# LED.net
KiCad netlist of a schematic drawn in Altium Designer
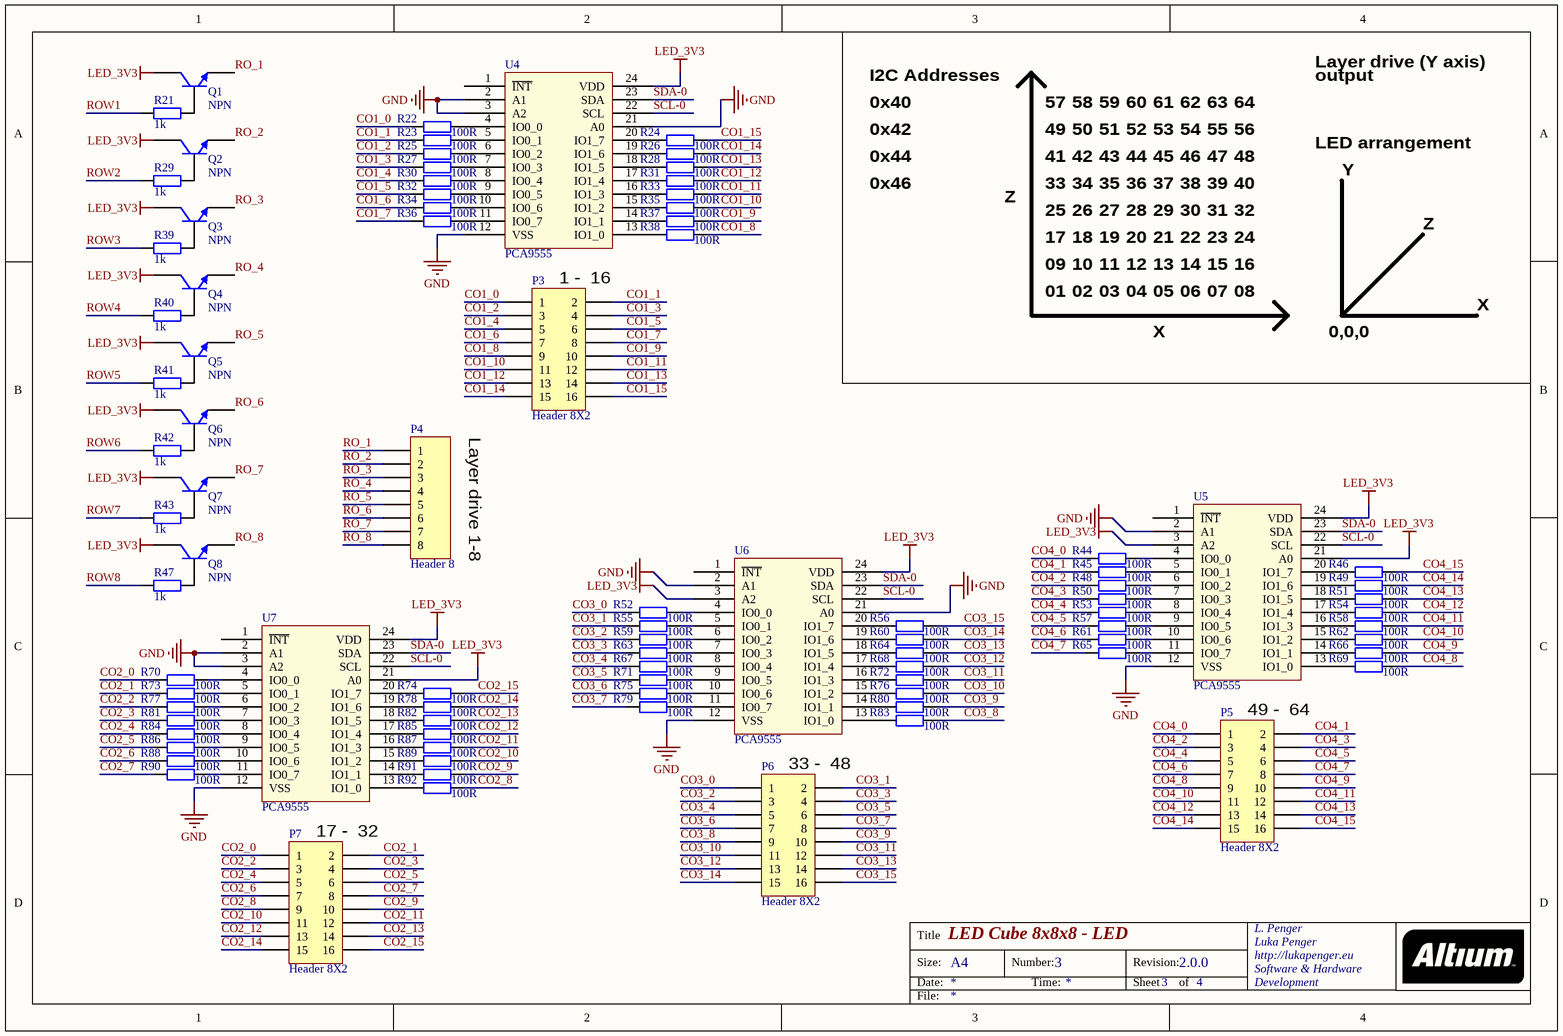
[diagram p0: LED.SchDoc]

(export (version "E")
  (design (tool "Eeschema 10.0.6"))
  (components
    (comp (ref "P3")
      (value "Header 8X2")
      (footprint "IDC-2x8")
      (description "Header, 8-Pin, Dual row")
      (fields (field (name "PUBLISHER") "Altium Limited"))
      (libsource (lib "Miscellaneous Connectors") (part "Header 8X2"))
    )
    (comp (ref "P4")
      (value "Header 8")
      (footprint "IDC-2x4")
      (description "Header, 8-Pin")
      (fields (field (name "PUBLISHER") "Altium Limited"))
      (libsource (lib "Miscellaneous Connectors") (part "Header 8"))
    )
    (comp (ref "P5")
      (value "Header 8X2")
      (footprint "IDC-2x8")
      (description "Header, 8-Pin, Dual row")
      (fields (field (name "PUBLISHER") "Altium Limited"))
      (libsource (lib "Miscellaneous Connectors") (part "Header 8X2"))
    )
    (comp (ref "P6")
      (value "Header 8X2")
      (footprint "IDC-2x8")
      (description "Header, 8-Pin, Dual row")
      (fields (field (name "PUBLISHER") "Altium Limited"))
      (libsource (lib "Miscellaneous Connectors") (part "Header 8X2"))
    )
    (comp (ref "P7")
      (value "Header 8X2")
      (footprint "IDC-2x8")
      (description "Header, 8-Pin, Dual row")
      (fields (field (name "PUBLISHER") "Altium Limited"))
      (libsource (lib "Miscellaneous Connectors") (part "Header 8X2"))
    )
    (comp (ref "Q1")
      (value "NPN")
      (footprint "SOT89N")
      (description "NPN Bipolar Transistor")
      (fields (field (name "PUBLISHER") "Altium Limited"))
      (libsource (lib "Miscellaneous Devices") (part "NPN"))
    )
    (comp (ref "Q2")
      (value "NPN")
      (footprint "SOT89N")
      (description "NPN Bipolar Transistor")
      (fields (field (name "PUBLISHER") "Altium Limited"))
      (libsource (lib "Miscellaneous Devices") (part "NPN"))
    )
    (comp (ref "Q3")
      (value "NPN")
      (footprint "SOT89N")
      (description "NPN Bipolar Transistor")
      (fields (field (name "PUBLISHER") "Altium Limited"))
      (libsource (lib "Miscellaneous Devices") (part "NPN"))
    )
    (comp (ref "Q4")
      (value "NPN")
      (footprint "SOT89N")
      (description "NPN Bipolar Transistor")
      (fields (field (name "PUBLISHER") "Altium Limited"))
      (libsource (lib "Miscellaneous Devices") (part "NPN"))
    )
    (comp (ref "Q5")
      (value "NPN")
      (footprint "SOT89N")
      (description "NPN Bipolar Transistor")
      (fields (field (name "PUBLISHER") "Altium Limited"))
      (libsource (lib "Miscellaneous Devices") (part "NPN"))
    )
    (comp (ref "Q6")
      (value "NPN")
      (footprint "SOT89N")
      (description "NPN Bipolar Transistor")
      (fields (field (name "PUBLISHER") "Altium Limited"))
      (libsource (lib "Miscellaneous Devices") (part "NPN"))
    )
    (comp (ref "Q7")
      (value "NPN")
      (footprint "SOT89N")
      (description "NPN Bipolar Transistor")
      (fields (field (name "PUBLISHER") "Altium Limited"))
      (libsource (lib "Miscellaneous Devices") (part "NPN"))
    )
    (comp (ref "Q8")
      (value "NPN")
      (footprint "SOT89N")
      (description "NPN Bipolar Transistor")
      (fields (field (name "PUBLISHER") "Altium Limited"))
      (libsource (lib "Miscellaneous Devices") (part "NPN"))
    )
    (comp (ref "R21")
      (value "1k")
      (footprint "6-0805_N")
      (description "Resistor")
      (fields (field (name "PUBLISHER") "Altium Limited"))
      (libsource (lib "") (part "Res2_1"))
    )
    (comp (ref "R22")
      (value "100R")
      (footprint "6-0805_N")
      (description "Resistor")
      (fields (field (name "PUBLISHER") "Altium Limited"))
      (libsource (lib "Miscellaneous Devices") (part "Res2"))
    )
    (comp (ref "R23")
      (value "100R")
      (footprint "6-0805_N")
      (description "Resistor")
      (fields (field (name "PUBLISHER") "Altium Limited"))
      (libsource (lib "Miscellaneous Devices") (part "Res2"))
    )
    (comp (ref "R24")
      (value "100R")
      (footprint "6-0805_N")
      (description "Resistor")
      (fields (field (name "PUBLISHER") "Altium Limited"))
      (libsource (lib "Miscellaneous Devices") (part "Res2"))
    )
    (comp (ref "R25")
      (value "100R")
      (footprint "6-0805_N")
      (description "Resistor")
      (fields (field (name "PUBLISHER") "Altium Limited"))
      (libsource (lib "Miscellaneous Devices") (part "Res2"))
    )
    (comp (ref "R26")
      (value "100R")
      (footprint "6-0805_N")
      (description "Resistor")
      (fields (field (name "PUBLISHER") "Altium Limited"))
      (libsource (lib "Miscellaneous Devices") (part "Res2"))
    )
    (comp (ref "R27")
      (value "100R")
      (footprint "6-0805_N")
      (description "Resistor")
      (fields (field (name "PUBLISHER") "Altium Limited"))
      (libsource (lib "Miscellaneous Devices") (part "Res2"))
    )
    (comp (ref "R28")
      (value "100R")
      (footprint "6-0805_N")
      (description "Resistor")
      (fields (field (name "PUBLISHER") "Altium Limited"))
      (libsource (lib "Miscellaneous Devices") (part "Res2"))
    )
    (comp (ref "R29")
      (value "1k")
      (footprint "6-0805_N")
      (description "Resistor")
      (fields (field (name "PUBLISHER") "Altium Limited"))
      (libsource (lib "") (part "Res2_1"))
    )
    (comp (ref "R30")
      (value "100R")
      (footprint "6-0805_N")
      (description "Resistor")
      (fields (field (name "PUBLISHER") "Altium Limited"))
      (libsource (lib "Miscellaneous Devices") (part "Res2"))
    )
    (comp (ref "R31")
      (value "100R")
      (footprint "6-0805_N")
      (description "Resistor")
      (fields (field (name "PUBLISHER") "Altium Limited"))
      (libsource (lib "Miscellaneous Devices") (part "Res2"))
    )
    (comp (ref "R32")
      (value "100R")
      (footprint "6-0805_N")
      (description "Resistor")
      (fields (field (name "PUBLISHER") "Altium Limited"))
      (libsource (lib "Miscellaneous Devices") (part "Res2"))
    )
    (comp (ref "R33")
      (value "100R")
      (footprint "6-0805_N")
      (description "Resistor")
      (fields (field (name "PUBLISHER") "Altium Limited"))
      (libsource (lib "Miscellaneous Devices") (part "Res2"))
    )
    (comp (ref "R34")
      (value "100R")
      (footprint "6-0805_N")
      (description "Resistor")
      (fields (field (name "PUBLISHER") "Altium Limited"))
      (libsource (lib "Miscellaneous Devices") (part "Res2"))
    )
    (comp (ref "R35")
      (value "100R")
      (footprint "6-0805_N")
      (description "Resistor")
      (fields (field (name "PUBLISHER") "Altium Limited"))
      (libsource (lib "Miscellaneous Devices") (part "Res2"))
    )
    (comp (ref "R36")
      (value "100R")
      (footprint "6-0805_N")
      (description "Resistor")
      (fields (field (name "PUBLISHER") "Altium Limited"))
      (libsource (lib "Miscellaneous Devices") (part "Res2"))
    )
    (comp (ref "R37")
      (value "100R")
      (footprint "6-0805_N")
      (description "Resistor")
      (fields (field (name "PUBLISHER") "Altium Limited"))
      (libsource (lib "Miscellaneous Devices") (part "Res2"))
    )
    (comp (ref "R38")
      (value "100R")
      (footprint "6-0805_N")
      (description "Resistor")
      (fields (field (name "PUBLISHER") "Altium Limited"))
      (libsource (lib "Miscellaneous Devices") (part "Res2"))
    )
    (comp (ref "R39")
      (value "1k")
      (footprint "6-0805_N")
      (description "Resistor")
      (fields (field (name "PUBLISHER") "Altium Limited"))
      (libsource (lib "") (part "Res2_1"))
    )
    (comp (ref "R40")
      (value "1k")
      (footprint "6-0805_N")
      (description "Resistor")
      (fields (field (name "PUBLISHER") "Altium Limited"))
      (libsource (lib "") (part "Res2_1"))
    )
    (comp (ref "R41")
      (value "1k")
      (footprint "6-0805_N")
      (description "Resistor")
      (fields (field (name "PUBLISHER") "Altium Limited"))
      (libsource (lib "") (part "Res2_1"))
    )
    (comp (ref "R42")
      (value "1k")
      (footprint "6-0805_N")
      (description "Resistor")
      (fields (field (name "PUBLISHER") "Altium Limited"))
      (libsource (lib "") (part "Res2_1"))
    )
    (comp (ref "R43")
      (value "1k")
      (footprint "6-0805_N")
      (description "Resistor")
      (fields (field (name "PUBLISHER") "Altium Limited"))
      (libsource (lib "") (part "Res2_1"))
    )
    (comp (ref "R44")
      (value "100R")
      (footprint "6-0805_N")
      (description "Resistor")
      (fields (field (name "PUBLISHER") "Altium Limited"))
      (libsource (lib "Miscellaneous Devices") (part "Res2"))
    )
    (comp (ref "R45")
      (value "100R")
      (footprint "6-0805_N")
      (description "Resistor")
      (fields (field (name "PUBLISHER") "Altium Limited"))
      (libsource (lib "Miscellaneous Devices") (part "Res2"))
    )
    (comp (ref "R46")
      (value "100R")
      (footprint "6-0805_N")
      (description "Resistor")
      (fields (field (name "PUBLISHER") "Altium Limited"))
      (libsource (lib "Miscellaneous Devices") (part "Res2"))
    )
    (comp (ref "R47")
      (value "1k")
      (footprint "6-0805_N")
      (description "Resistor")
      (fields (field (name "PUBLISHER") "Altium Limited"))
      (libsource (lib "") (part "Res2_1"))
    )
    (comp (ref "R48")
      (value "100R")
      (footprint "6-0805_N")
      (description "Resistor")
      (fields (field (name "PUBLISHER") "Altium Limited"))
      (libsource (lib "Miscellaneous Devices") (part "Res2"))
    )
    (comp (ref "R49")
      (value "100R")
      (footprint "6-0805_N")
      (description "Resistor")
      (fields (field (name "PUBLISHER") "Altium Limited"))
      (libsource (lib "Miscellaneous Devices") (part "Res2"))
    )
    (comp (ref "R50")
      (value "100R")
      (footprint "6-0805_N")
      (description "Resistor")
      (fields (field (name "PUBLISHER") "Altium Limited"))
      (libsource (lib "Miscellaneous Devices") (part "Res2"))
    )
    (comp (ref "R51")
      (value "100R")
      (footprint "6-0805_N")
      (description "Resistor")
      (fields (field (name "PUBLISHER") "Altium Limited"))
      (libsource (lib "Miscellaneous Devices") (part "Res2"))
    )
    (comp (ref "R52")
      (value "100R")
      (footprint "6-0805_N")
      (description "Resistor")
      (fields (field (name "PUBLISHER") "Altium Limited"))
      (libsource (lib "Miscellaneous Devices") (part "Res2"))
    )
    (comp (ref "R53")
      (value "100R")
      (footprint "6-0805_N")
      (description "Resistor")
      (fields (field (name "PUBLISHER") "Altium Limited"))
      (libsource (lib "Miscellaneous Devices") (part "Res2"))
    )
    (comp (ref "R54")
      (value "100R")
      (footprint "6-0805_N")
      (description "Resistor")
      (fields (field (name "PUBLISHER") "Altium Limited"))
      (libsource (lib "Miscellaneous Devices") (part "Res2"))
    )
    (comp (ref "R55")
      (value "100R")
      (footprint "6-0805_N")
      (description "Resistor")
      (fields (field (name "PUBLISHER") "Altium Limited"))
      (libsource (lib "Miscellaneous Devices") (part "Res2"))
    )
    (comp (ref "R56")
      (value "100R")
      (footprint "6-0805_N")
      (description "Resistor")
      (fields (field (name "PUBLISHER") "Altium Limited"))
      (libsource (lib "Miscellaneous Devices") (part "Res2"))
    )
    (comp (ref "R57")
      (value "100R")
      (footprint "6-0805_N")
      (description "Resistor")
      (fields (field (name "PUBLISHER") "Altium Limited"))
      (libsource (lib "Miscellaneous Devices") (part "Res2"))
    )
    (comp (ref "R58")
      (value "100R")
      (footprint "6-0805_N")
      (description "Resistor")
      (fields (field (name "PUBLISHER") "Altium Limited"))
      (libsource (lib "Miscellaneous Devices") (part "Res2"))
    )
    (comp (ref "R59")
      (value "100R")
      (footprint "6-0805_N")
      (description "Resistor")
      (fields (field (name "PUBLISHER") "Altium Limited"))
      (libsource (lib "Miscellaneous Devices") (part "Res2"))
    )
    (comp (ref "R60")
      (value "100R")
      (footprint "6-0805_N")
      (description "Resistor")
      (fields (field (name "PUBLISHER") "Altium Limited"))
      (libsource (lib "Miscellaneous Devices") (part "Res2"))
    )
    (comp (ref "R61")
      (value "100R")
      (footprint "6-0805_N")
      (description "Resistor")
      (fields (field (name "PUBLISHER") "Altium Limited"))
      (libsource (lib "Miscellaneous Devices") (part "Res2"))
    )
    (comp (ref "R62")
      (value "100R")
      (footprint "6-0805_N")
      (description "Resistor")
      (fields (field (name "PUBLISHER") "Altium Limited"))
      (libsource (lib "Miscellaneous Devices") (part "Res2"))
    )
    (comp (ref "R63")
      (value "100R")
      (footprint "6-0805_N")
      (description "Resistor")
      (fields (field (name "PUBLISHER") "Altium Limited"))
      (libsource (lib "Miscellaneous Devices") (part "Res2"))
    )
    (comp (ref "R64")
      (value "100R")
      (footprint "6-0805_N")
      (description "Resistor")
      (fields (field (name "PUBLISHER") "Altium Limited"))
      (libsource (lib "Miscellaneous Devices") (part "Res2"))
    )
    (comp (ref "R65")
      (value "100R")
      (footprint "6-0805_N")
      (description "Resistor")
      (fields (field (name "PUBLISHER") "Altium Limited"))
      (libsource (lib "Miscellaneous Devices") (part "Res2"))
    )
    (comp (ref "R66")
      (value "100R")
      (footprint "6-0805_N")
      (description "Resistor")
      (fields (field (name "PUBLISHER") "Altium Limited"))
      (libsource (lib "Miscellaneous Devices") (part "Res2"))
    )
    (comp (ref "R67")
      (value "100R")
      (footprint "6-0805_N")
      (description "Resistor")
      (fields (field (name "PUBLISHER") "Altium Limited"))
      (libsource (lib "Miscellaneous Devices") (part "Res2"))
    )
    (comp (ref "R68")
      (value "100R")
      (footprint "6-0805_N")
      (description "Resistor")
      (fields (field (name "PUBLISHER") "Altium Limited"))
      (libsource (lib "Miscellaneous Devices") (part "Res2"))
    )
    (comp (ref "R69")
      (value "100R")
      (footprint "6-0805_N")
      (description "Resistor")
      (fields (field (name "PUBLISHER") "Altium Limited"))
      (libsource (lib "Miscellaneous Devices") (part "Res2"))
    )
    (comp (ref "R70")
      (value "100R")
      (footprint "6-0805_N")
      (description "Resistor")
      (fields (field (name "PUBLISHER") "Altium Limited"))
      (libsource (lib "Miscellaneous Devices") (part "Res2"))
    )
    (comp (ref "R71")
      (value "100R")
      (footprint "6-0805_N")
      (description "Resistor")
      (fields (field (name "PUBLISHER") "Altium Limited"))
      (libsource (lib "Miscellaneous Devices") (part "Res2"))
    )
    (comp (ref "R72")
      (value "100R")
      (footprint "6-0805_N")
      (description "Resistor")
      (fields (field (name "PUBLISHER") "Altium Limited"))
      (libsource (lib "Miscellaneous Devices") (part "Res2"))
    )
    (comp (ref "R73")
      (value "100R")
      (footprint "6-0805_N")
      (description "Resistor")
      (fields (field (name "PUBLISHER") "Altium Limited"))
      (libsource (lib "Miscellaneous Devices") (part "Res2"))
    )
    (comp (ref "R74")
      (value "100R")
      (footprint "6-0805_N")
      (description "Resistor")
      (fields (field (name "PUBLISHER") "Altium Limited"))
      (libsource (lib "Miscellaneous Devices") (part "Res2"))
    )
    (comp (ref "R75")
      (value "100R")
      (footprint "6-0805_N")
      (description "Resistor")
      (fields (field (name "PUBLISHER") "Altium Limited"))
      (libsource (lib "Miscellaneous Devices") (part "Res2"))
    )
    (comp (ref "R76")
      (value "100R")
      (footprint "6-0805_N")
      (description "Resistor")
      (fields (field (name "PUBLISHER") "Altium Limited"))
      (libsource (lib "Miscellaneous Devices") (part "Res2"))
    )
    (comp (ref "R77")
      (value "100R")
      (footprint "6-0805_N")
      (description "Resistor")
      (fields (field (name "PUBLISHER") "Altium Limited"))
      (libsource (lib "Miscellaneous Devices") (part "Res2"))
    )
    (comp (ref "R78")
      (value "100R")
      (footprint "6-0805_N")
      (description "Resistor")
      (fields (field (name "PUBLISHER") "Altium Limited"))
      (libsource (lib "Miscellaneous Devices") (part "Res2"))
    )
    (comp (ref "R79")
      (value "100R")
      (footprint "6-0805_N")
      (description "Resistor")
      (fields (field (name "PUBLISHER") "Altium Limited"))
      (libsource (lib "Miscellaneous Devices") (part "Res2"))
    )
    (comp (ref "R80")
      (value "100R")
      (footprint "6-0805_N")
      (description "Resistor")
      (fields (field (name "PUBLISHER") "Altium Limited"))
      (libsource (lib "Miscellaneous Devices") (part "Res2"))
    )
    (comp (ref "R81")
      (value "100R")
      (footprint "6-0805_N")
      (description "Resistor")
      (fields (field (name "PUBLISHER") "Altium Limited"))
      (libsource (lib "Miscellaneous Devices") (part "Res2"))
    )
    (comp (ref "R82")
      (value "100R")
      (footprint "6-0805_N")
      (description "Resistor")
      (fields (field (name "PUBLISHER") "Altium Limited"))
      (libsource (lib "Miscellaneous Devices") (part "Res2"))
    )
    (comp (ref "R83")
      (value "100R")
      (footprint "6-0805_N")
      (description "Resistor")
      (fields (field (name "PUBLISHER") "Altium Limited"))
      (libsource (lib "Miscellaneous Devices") (part "Res2"))
    )
    (comp (ref "R84")
      (value "100R")
      (footprint "6-0805_N")
      (description "Resistor")
      (fields (field (name "PUBLISHER") "Altium Limited"))
      (libsource (lib "Miscellaneous Devices") (part "Res2"))
    )
    (comp (ref "R85")
      (value "100R")
      (footprint "6-0805_N")
      (description "Resistor")
      (fields (field (name "PUBLISHER") "Altium Limited"))
      (libsource (lib "Miscellaneous Devices") (part "Res2"))
    )
    (comp (ref "R86")
      (value "100R")
      (footprint "6-0805_N")
      (description "Resistor")
      (fields (field (name "PUBLISHER") "Altium Limited"))
      (libsource (lib "Miscellaneous Devices") (part "Res2"))
    )
    (comp (ref "R87")
      (value "100R")
      (footprint "6-0805_N")
      (description "Resistor")
      (fields (field (name "PUBLISHER") "Altium Limited"))
      (libsource (lib "Miscellaneous Devices") (part "Res2"))
    )
    (comp (ref "R88")
      (value "100R")
      (footprint "6-0805_N")
      (description "Resistor")
      (fields (field (name "PUBLISHER") "Altium Limited"))
      (libsource (lib "Miscellaneous Devices") (part "Res2"))
    )
    (comp (ref "R89")
      (value "100R")
      (footprint "6-0805_N")
      (description "Resistor")
      (fields (field (name "PUBLISHER") "Altium Limited"))
      (libsource (lib "Miscellaneous Devices") (part "Res2"))
    )
    (comp (ref "R90")
      (value "100R")
      (footprint "6-0805_N")
      (description "Resistor")
      (fields (field (name "PUBLISHER") "Altium Limited"))
      (libsource (lib "Miscellaneous Devices") (part "Res2"))
    )
    (comp (ref "R91")
      (value "100R")
      (footprint "6-0805_N")
      (description "Resistor")
      (fields (field (name "PUBLISHER") "Altium Limited"))
      (libsource (lib "Miscellaneous Devices") (part "Res2"))
    )
    (comp (ref "R92")
      (value "100R")
      (footprint "6-0805_N")
      (description "Resistor")
      (fields (field (name "PUBLISHER") "Altium Limited"))
      (libsource (lib "Miscellaneous Devices") (part "Res2"))
    )
    (comp (ref "U4")
      (value "PCA9555")
      (footprint "SSOP24_N")
      (description "I2C I/O Ports")
      (libsource (lib "LP_Lib") (part "PCA9555"))
    )
    (comp (ref "U5")
      (value "PCA9555")
      (footprint "SSOP24_N")
      (description "I2C I/O Ports")
      (libsource (lib "LP_Lib") (part "PCA9555"))
    )
    (comp (ref "U6")
      (value "PCA9555")
      (footprint "SSOP24_N")
      (description "I2C I/O Ports")
      (libsource (lib "LP_Lib") (part "PCA9555"))
    )
    (comp (ref "U7")
      (value "PCA9555")
      (footprint "SSOP24_N")
      (description "I2C I/O Ports")
      (libsource (lib "LP_Lib") (part "PCA9555"))
    )
  )
  (nets
    (net (code "1") (name "/CO1_0") (class "Default")
      (node (ref "P3") (pin "1") (pinfunction "1_1") (pintype "passive"))
      (node (ref "R22") (pin "1") (pinfunction "1_1") (pintype "passive"))
    )
    (net (code "2") (name "/CO1_1") (class "Default")
      (node (ref "P3") (pin "2") (pinfunction "2_2") (pintype "passive"))
      (node (ref "R23") (pin "1") (pinfunction "1_1") (pintype "passive"))
    )
    (net (code "3") (name "/CO1_2") (class "Default")
      (node (ref "P3") (pin "3") (pinfunction "3_3") (pintype "passive"))
      (node (ref "R25") (pin "1") (pinfunction "1_1") (pintype "passive"))
    )
    (net (code "4") (name "/CO1_3") (class "Default")
      (node (ref "P3") (pin "4") (pinfunction "4_4") (pintype "passive"))
      (node (ref "R27") (pin "1") (pinfunction "1_1") (pintype "passive"))
    )
    (net (code "5") (name "/CO1_4") (class "Default")
      (node (ref "P3") (pin "5") (pinfunction "5_5") (pintype "passive"))
      (node (ref "R30") (pin "1") (pinfunction "1_1") (pintype "passive"))
    )
    (net (code "6") (name "/CO1_5") (class "Default")
      (node (ref "P3") (pin "6") (pinfunction "6_6") (pintype "passive"))
      (node (ref "R32") (pin "1") (pinfunction "1_1") (pintype "passive"))
    )
    (net (code "7") (name "/CO1_6") (class "Default")
      (node (ref "P3") (pin "7") (pinfunction "7_7") (pintype "passive"))
      (node (ref "R34") (pin "1") (pinfunction "1_1") (pintype "passive"))
    )
    (net (code "8") (name "/CO1_7") (class "Default")
      (node (ref "P3") (pin "8") (pinfunction "8_8") (pintype "passive"))
      (node (ref "R36") (pin "1") (pinfunction "1_1") (pintype "passive"))
    )
    (net (code "9") (name "/CO1_8") (class "Default")
      (node (ref "P3") (pin "9") (pinfunction "9_9") (pintype "passive"))
      (node (ref "R38") (pin "2") (pinfunction "2_2") (pintype "passive"))
    )
    (net (code "10") (name "/CO1_9") (class "Default")
      (node (ref "P3") (pin "10") (pinfunction "10_10") (pintype "passive"))
      (node (ref "R37") (pin "2") (pinfunction "2_2") (pintype "passive"))
    )
    (net (code "11") (name "/CO1_10") (class "Default")
      (node (ref "P3") (pin "11") (pinfunction "11_11") (pintype "passive"))
      (node (ref "R35") (pin "2") (pinfunction "2_2") (pintype "passive"))
    )
    (net (code "12") (name "/CO1_11") (class "Default")
      (node (ref "P3") (pin "12") (pinfunction "12_12") (pintype "passive"))
      (node (ref "R33") (pin "2") (pinfunction "2_2") (pintype "passive"))
    )
    (net (code "13") (name "/CO1_12") (class "Default")
      (node (ref "P3") (pin "13") (pinfunction "13_13") (pintype "passive"))
      (node (ref "R31") (pin "2") (pinfunction "2_2") (pintype "passive"))
    )
    (net (code "14") (name "/CO1_13") (class "Default")
      (node (ref "P3") (pin "14") (pinfunction "14_14") (pintype "passive"))
      (node (ref "R28") (pin "2") (pinfunction "2_2") (pintype "passive"))
    )
    (net (code "15") (name "/CO1_14") (class "Default")
      (node (ref "P3") (pin "15") (pinfunction "15_15") (pintype "passive"))
      (node (ref "R26") (pin "2") (pinfunction "2_2") (pintype "passive"))
    )
    (net (code "16") (name "/CO1_15") (class "Default")
      (node (ref "P3") (pin "16") (pinfunction "16_16") (pintype "passive"))
      (node (ref "R24") (pin "2") (pinfunction "2_2") (pintype "passive"))
    )
    (net (code "17") (name "/CO2_0") (class "Default")
      (node (ref "P7") (pin "1") (pinfunction "1_1") (pintype "passive"))
      (node (ref "R70") (pin "1") (pinfunction "1_1") (pintype "passive"))
    )
    (net (code "18") (name "/CO2_1") (class "Default")
      (node (ref "P7") (pin "2") (pinfunction "2_2") (pintype "passive"))
      (node (ref "R73") (pin "1") (pinfunction "1_1") (pintype "passive"))
    )
    (net (code "19") (name "/CO2_2") (class "Default")
      (node (ref "P7") (pin "3") (pinfunction "3_3") (pintype "passive"))
      (node (ref "R77") (pin "1") (pinfunction "1_1") (pintype "passive"))
    )
    (net (code "20") (name "/CO2_3") (class "Default")
      (node (ref "P7") (pin "4") (pinfunction "4_4") (pintype "passive"))
      (node (ref "R81") (pin "1") (pinfunction "1_1") (pintype "passive"))
    )
    (net (code "21") (name "/CO2_4") (class "Default")
      (node (ref "P7") (pin "5") (pinfunction "5_5") (pintype "passive"))
      (node (ref "R84") (pin "1") (pinfunction "1_1") (pintype "passive"))
    )
    (net (code "22") (name "/CO2_5") (class "Default")
      (node (ref "P7") (pin "6") (pinfunction "6_6") (pintype "passive"))
      (node (ref "R86") (pin "1") (pinfunction "1_1") (pintype "passive"))
    )
    (net (code "23") (name "/CO2_6") (class "Default")
      (node (ref "P7") (pin "7") (pinfunction "7_7") (pintype "passive"))
      (node (ref "R88") (pin "1") (pinfunction "1_1") (pintype "passive"))
    )
    (net (code "24") (name "/CO2_7") (class "Default")
      (node (ref "P7") (pin "8") (pinfunction "8_8") (pintype "passive"))
      (node (ref "R90") (pin "1") (pinfunction "1_1") (pintype "passive"))
    )
    (net (code "25") (name "/CO2_8") (class "Default")
      (node (ref "P7") (pin "9") (pinfunction "9_9") (pintype "passive"))
      (node (ref "R92") (pin "2") (pinfunction "2_2") (pintype "passive"))
    )
    (net (code "26") (name "/CO2_9") (class "Default")
      (node (ref "P7") (pin "10") (pinfunction "10_10") (pintype "passive"))
      (node (ref "R91") (pin "2") (pinfunction "2_2") (pintype "passive"))
    )
    (net (code "27") (name "/CO2_10") (class "Default")
      (node (ref "P7") (pin "11") (pinfunction "11_11") (pintype "passive"))
      (node (ref "R89") (pin "2") (pinfunction "2_2") (pintype "passive"))
    )
    (net (code "28") (name "/CO2_11") (class "Default")
      (node (ref "P7") (pin "12") (pinfunction "12_12") (pintype "passive"))
      (node (ref "R87") (pin "2") (pinfunction "2_2") (pintype "passive"))
    )
    (net (code "29") (name "/CO2_12") (class "Default")
      (node (ref "P7") (pin "13") (pinfunction "13_13") (pintype "passive"))
      (node (ref "R85") (pin "2") (pinfunction "2_2") (pintype "passive"))
    )
    (net (code "30") (name "/CO2_13") (class "Default")
      (node (ref "P7") (pin "14") (pinfunction "14_14") (pintype "passive"))
      (node (ref "R82") (pin "2") (pinfunction "2_2") (pintype "passive"))
    )
    (net (code "31") (name "/CO2_14") (class "Default")
      (node (ref "P7") (pin "15") (pinfunction "15_15") (pintype "passive"))
      (node (ref "R78") (pin "2") (pinfunction "2_2") (pintype "passive"))
    )
    (net (code "32") (name "/CO2_15") (class "Default")
      (node (ref "P7") (pin "16") (pinfunction "16_16") (pintype "passive"))
      (node (ref "R74") (pin "2") (pinfunction "2_2") (pintype "passive"))
    )
    (net (code "33") (name "/CO3_0") (class "Default")
      (node (ref "P6") (pin "1") (pinfunction "1_1") (pintype "passive"))
      (node (ref "R52") (pin "1") (pinfunction "1_1") (pintype "passive"))
    )
    (net (code "34") (name "/CO3_1") (class "Default")
      (node (ref "P6") (pin "2") (pinfunction "2_2") (pintype "passive"))
      (node (ref "R55") (pin "1") (pinfunction "1_1") (pintype "passive"))
    )
    (net (code "35") (name "/CO3_2") (class "Default")
      (node (ref "P6") (pin "3") (pinfunction "3_3") (pintype "passive"))
      (node (ref "R59") (pin "1") (pinfunction "1_1") (pintype "passive"))
    )
    (net (code "36") (name "/CO3_3") (class "Default")
      (node (ref "P6") (pin "4") (pinfunction "4_4") (pintype "passive"))
      (node (ref "R63") (pin "1") (pinfunction "1_1") (pintype "passive"))
    )
    (net (code "37") (name "/CO3_4") (class "Default")
      (node (ref "P6") (pin "5") (pinfunction "5_5") (pintype "passive"))
      (node (ref "R67") (pin "1") (pinfunction "1_1") (pintype "passive"))
    )
    (net (code "38") (name "/CO3_5") (class "Default")
      (node (ref "P6") (pin "6") (pinfunction "6_6") (pintype "passive"))
      (node (ref "R71") (pin "1") (pinfunction "1_1") (pintype "passive"))
    )
    (net (code "39") (name "/CO3_6") (class "Default")
      (node (ref "P6") (pin "7") (pinfunction "7_7") (pintype "passive"))
      (node (ref "R75") (pin "1") (pinfunction "1_1") (pintype "passive"))
    )
    (net (code "40") (name "/CO3_7") (class "Default")
      (node (ref "P6") (pin "8") (pinfunction "8_8") (pintype "passive"))
      (node (ref "R79") (pin "1") (pinfunction "1_1") (pintype "passive"))
    )
    (net (code "41") (name "/CO3_8") (class "Default")
      (node (ref "P6") (pin "9") (pinfunction "9_9") (pintype "passive"))
      (node (ref "R83") (pin "2") (pinfunction "2_2") (pintype "passive"))
    )
    (net (code "42") (name "/CO3_9") (class "Default")
      (node (ref "P6") (pin "10") (pinfunction "10_10") (pintype "passive"))
      (node (ref "R80") (pin "2") (pinfunction "2_2") (pintype "passive"))
    )
    (net (code "43") (name "/CO3_10") (class "Default")
      (node (ref "P6") (pin "11") (pinfunction "11_11") (pintype "passive"))
      (node (ref "R76") (pin "2") (pinfunction "2_2") (pintype "passive"))
    )
    (net (code "44") (name "/CO3_11") (class "Default")
      (node (ref "P6") (pin "12") (pinfunction "12_12") (pintype "passive"))
      (node (ref "R72") (pin "2") (pinfunction "2_2") (pintype "passive"))
    )
    (net (code "45") (name "/CO3_12") (class "Default")
      (node (ref "P6") (pin "13") (pinfunction "13_13") (pintype "passive"))
      (node (ref "R68") (pin "2") (pinfunction "2_2") (pintype "passive"))
    )
    (net (code "46") (name "/CO3_13") (class "Default")
      (node (ref "P6") (pin "14") (pinfunction "14_14") (pintype "passive"))
      (node (ref "R64") (pin "2") (pinfunction "2_2") (pintype "passive"))
    )
    (net (code "47") (name "/CO3_14") (class "Default")
      (node (ref "P6") (pin "15") (pinfunction "15_15") (pintype "passive"))
      (node (ref "R60") (pin "2") (pinfunction "2_2") (pintype "passive"))
    )
    (net (code "48") (name "/CO3_15") (class "Default")
      (node (ref "P6") (pin "16") (pinfunction "16_16") (pintype "passive"))
      (node (ref "R56") (pin "2") (pinfunction "2_2") (pintype "passive"))
    )
    (net (code "49") (name "/CO4_0") (class "Default")
      (node (ref "P5") (pin "1") (pinfunction "1_1") (pintype "passive"))
      (node (ref "R44") (pin "1") (pinfunction "1_1") (pintype "passive"))
    )
    (net (code "50") (name "/CO4_1") (class "Default")
      (node (ref "P5") (pin "2") (pinfunction "2_2") (pintype "passive"))
      (node (ref "R45") (pin "1") (pinfunction "1_1") (pintype "passive"))
    )
    (net (code "51") (name "/CO4_2") (class "Default")
      (node (ref "P5") (pin "3") (pinfunction "3_3") (pintype "passive"))
      (node (ref "R48") (pin "1") (pinfunction "1_1") (pintype "passive"))
    )
    (net (code "52") (name "/CO4_3") (class "Default")
      (node (ref "P5") (pin "4") (pinfunction "4_4") (pintype "passive"))
      (node (ref "R50") (pin "1") (pinfunction "1_1") (pintype "passive"))
    )
    (net (code "53") (name "/CO4_4") (class "Default")
      (node (ref "P5") (pin "5") (pinfunction "5_5") (pintype "passive"))
      (node (ref "R53") (pin "1") (pinfunction "1_1") (pintype "passive"))
    )
    (net (code "54") (name "/CO4_5") (class "Default")
      (node (ref "P5") (pin "6") (pinfunction "6_6") (pintype "passive"))
      (node (ref "R57") (pin "1") (pinfunction "1_1") (pintype "passive"))
    )
    (net (code "55") (name "/CO4_6") (class "Default")
      (node (ref "P5") (pin "7") (pinfunction "7_7") (pintype "passive"))
      (node (ref "R61") (pin "1") (pinfunction "1_1") (pintype "passive"))
    )
    (net (code "56") (name "/CO4_7") (class "Default")
      (node (ref "P5") (pin "8") (pinfunction "8_8") (pintype "passive"))
      (node (ref "R65") (pin "1") (pinfunction "1_1") (pintype "passive"))
    )
    (net (code "57") (name "/CO4_8") (class "Default")
      (node (ref "P5") (pin "9") (pinfunction "9_9") (pintype "passive"))
      (node (ref "R69") (pin "2") (pinfunction "2_2") (pintype "passive"))
    )
    (net (code "58") (name "/CO4_9") (class "Default")
      (node (ref "P5") (pin "10") (pinfunction "10_10") (pintype "passive"))
      (node (ref "R66") (pin "2") (pinfunction "2_2") (pintype "passive"))
    )
    (net (code "59") (name "/CO4_10") (class "Default")
      (node (ref "P5") (pin "11") (pinfunction "11_11") (pintype "passive"))
      (node (ref "R62") (pin "2") (pinfunction "2_2") (pintype "passive"))
    )
    (net (code "60") (name "/CO4_11") (class "Default")
      (node (ref "P5") (pin "12") (pinfunction "12_12") (pintype "passive"))
      (node (ref "R58") (pin "2") (pinfunction "2_2") (pintype "passive"))
    )
    (net (code "61") (name "/CO4_12") (class "Default")
      (node (ref "P5") (pin "13") (pinfunction "13_13") (pintype "passive"))
      (node (ref "R54") (pin "2") (pinfunction "2_2") (pintype "passive"))
    )
    (net (code "62") (name "/CO4_13") (class "Default")
      (node (ref "P5") (pin "14") (pinfunction "14_14") (pintype "passive"))
      (node (ref "R51") (pin "2") (pinfunction "2_2") (pintype "passive"))
    )
    (net (code "63") (name "/CO4_14") (class "Default")
      (node (ref "P5") (pin "15") (pinfunction "15_15") (pintype "passive"))
      (node (ref "R49") (pin "2") (pinfunction "2_2") (pintype "passive"))
    )
    (net (code "64") (name "/CO4_15") (class "Default")
      (node (ref "P5") (pin "16") (pinfunction "16_16") (pintype "passive"))
      (node (ref "R46") (pin "2") (pinfunction "2_2") (pintype "passive"))
    )
    (net (code "65") (name "/ROW1") (class "Default")
      (node (ref "R21") (pin "2") (pinfunction "2_2") (pintype "passive"))
    )
    (net (code "66") (name "/ROW2") (class "Default")
      (node (ref "R29") (pin "2") (pinfunction "2_2") (pintype "passive"))
    )
    (net (code "67") (name "/ROW3") (class "Default")
      (node (ref "R39") (pin "2") (pinfunction "2_2") (pintype "passive"))
    )
    (net (code "68") (name "/ROW4") (class "Default")
      (node (ref "R40") (pin "2") (pinfunction "2_2") (pintype "passive"))
    )
    (net (code "69") (name "/ROW5") (class "Default")
      (node (ref "R41") (pin "2") (pinfunction "2_2") (pintype "passive"))
    )
    (net (code "70") (name "/ROW6") (class "Default")
      (node (ref "R42") (pin "2") (pinfunction "2_2") (pintype "passive"))
    )
    (net (code "71") (name "/ROW7") (class "Default")
      (node (ref "R43") (pin "2") (pinfunction "2_2") (pintype "passive"))
    )
    (net (code "72") (name "/ROW8") (class "Default")
      (node (ref "R47") (pin "2") (pinfunction "2_2") (pintype "passive"))
    )
    (net (code "73") (name "/RO_1") (class "Default")
      (node (ref "P4") (pin "1") (pinfunction "1_1") (pintype "passive"))
      (node (ref "Q1") (pin "3") (pinfunction "E_3") (pintype "passive"))
    )
    (net (code "74") (name "/RO_2") (class "Default")
      (node (ref "P4") (pin "2") (pinfunction "2_2") (pintype "passive"))
      (node (ref "Q2") (pin "3") (pinfunction "E_3") (pintype "passive"))
    )
    (net (code "75") (name "/RO_3") (class "Default")
      (node (ref "P4") (pin "3") (pinfunction "3_3") (pintype "passive"))
      (node (ref "Q3") (pin "3") (pinfunction "E_3") (pintype "passive"))
    )
    (net (code "76") (name "/RO_4") (class "Default")
      (node (ref "P4") (pin "4") (pinfunction "4_4") (pintype "passive"))
      (node (ref "Q4") (pin "3") (pinfunction "E_3") (pintype "passive"))
    )
    (net (code "77") (name "/RO_5") (class "Default")
      (node (ref "P4") (pin "5") (pinfunction "5_5") (pintype "passive"))
      (node (ref "Q5") (pin "3") (pinfunction "E_3") (pintype "passive"))
    )
    (net (code "78") (name "/RO_6") (class "Default")
      (node (ref "P4") (pin "6") (pinfunction "6_6") (pintype "passive"))
      (node (ref "Q6") (pin "3") (pinfunction "E_3") (pintype "passive"))
    )
    (net (code "79") (name "/RO_7") (class "Default")
      (node (ref "P4") (pin "7") (pinfunction "7_7") (pintype "passive"))
      (node (ref "Q7") (pin "3") (pinfunction "E_3") (pintype "passive"))
    )
    (net (code "80") (name "/RO_8") (class "Default")
      (node (ref "P4") (pin "8") (pinfunction "8_8") (pintype "passive"))
      (node (ref "Q8") (pin "3") (pinfunction "E_3") (pintype "passive"))
    )
    (net (code "81") (name "/SCL-0") (class "Default")
      (node (ref "U4") (pin "22") (pinfunction "SCL_22") (pintype "passive"))
      (node (ref "U5") (pin "22") (pinfunction "SCL_22") (pintype "passive"))
      (node (ref "U6") (pin "22") (pinfunction "SCL_22") (pintype "passive"))
      (node (ref "U7") (pin "22") (pinfunction "SCL_22") (pintype "passive"))
    )
    (net (code "82") (name "/SDA-0") (class "Default")
      (node (ref "U4") (pin "23") (pinfunction "SDA_23") (pintype "passive"))
      (node (ref "U5") (pin "23") (pinfunction "SDA_23") (pintype "passive"))
      (node (ref "U6") (pin "23") (pinfunction "SDA_23") (pintype "passive"))
      (node (ref "U7") (pin "23") (pinfunction "SDA_23") (pintype "passive"))
    )
    (net (code "83") (name "GND") (class "Default")
      (node (ref "U4") (pin "12") (pinfunction "VSS_12") (pintype "passive"))
      (node (ref "U4") (pin "2") (pinfunction "A1_2") (pintype "passive"))
      (node (ref "U4") (pin "21") (pinfunction "A0_21") (pintype "passive"))
      (node (ref "U4") (pin "3") (pinfunction "A2_3") (pintype "passive"))
      (node (ref "U5") (pin "12") (pinfunction "VSS_12") (pintype "passive"))
      (node (ref "U5") (pin "2") (pinfunction "A1_2") (pintype "passive"))
      (node (ref "U6") (pin "12") (pinfunction "VSS_12") (pintype "passive"))
      (node (ref "U6") (pin "2") (pinfunction "A1_2") (pintype "passive"))
      (node (ref "U6") (pin "21") (pinfunction "A0_21") (pintype "passive"))
      (node (ref "U7") (pin "12") (pinfunction "VSS_12") (pintype "passive"))
      (node (ref "U7") (pin "2") (pinfunction "A1_2") (pintype "passive"))
      (node (ref "U7") (pin "3") (pinfunction "A2_3") (pintype "passive"))
    )
    (net (code "84") (name "LED_3V3") (class "Default")
      (node (ref "Q1") (pin "1") (pinfunction "C_1") (pintype "passive"))
      (node (ref "Q2") (pin "1") (pinfunction "C_1") (pintype "passive"))
      (node (ref "Q3") (pin "1") (pinfunction "C_1") (pintype "passive"))
      (node (ref "Q4") (pin "1") (pinfunction "C_1") (pintype "passive"))
      (node (ref "Q5") (pin "1") (pinfunction "C_1") (pintype "passive"))
      (node (ref "Q6") (pin "1") (pinfunction "C_1") (pintype "passive"))
      (node (ref "Q7") (pin "1") (pinfunction "C_1") (pintype "passive"))
      (node (ref "Q8") (pin "1") (pinfunction "C_1") (pintype "passive"))
      (node (ref "U4") (pin "24") (pinfunction "VDD_24") (pintype "passive"))
      (node (ref "U5") (pin "21") (pinfunction "A0_21") (pintype "passive"))
      (node (ref "U5") (pin "24") (pinfunction "VDD_24") (pintype "passive"))
      (node (ref "U5") (pin "3") (pinfunction "A2_3") (pintype "passive"))
      (node (ref "U6") (pin "24") (pinfunction "VDD_24") (pintype "passive"))
      (node (ref "U6") (pin "3") (pinfunction "A2_3") (pintype "passive"))
      (node (ref "U7") (pin "21") (pinfunction "A0_21") (pintype "passive"))
      (node (ref "U7") (pin "24") (pinfunction "VDD_24") (pintype "passive"))
    )
    (net (code "85") (name "Net-(Q1-B)") (class "Default")
      (node (ref "Q1") (pin "2") (pinfunction "B_2") (pintype "passive"))
      (node (ref "R21") (pin "1") (pinfunction "1_1") (pintype "passive"))
    )
    (net (code "86") (name "Net-(Q2-B)") (class "Default")
      (node (ref "Q2") (pin "2") (pinfunction "B_2") (pintype "passive"))
      (node (ref "R29") (pin "1") (pinfunction "1_1") (pintype "passive"))
    )
    (net (code "87") (name "Net-(Q3-B)") (class "Default")
      (node (ref "Q3") (pin "2") (pinfunction "B_2") (pintype "passive"))
      (node (ref "R39") (pin "1") (pinfunction "1_1") (pintype "passive"))
    )
    (net (code "88") (name "Net-(Q4-B)") (class "Default")
      (node (ref "Q4") (pin "2") (pinfunction "B_2") (pintype "passive"))
      (node (ref "R40") (pin "1") (pinfunction "1_1") (pintype "passive"))
    )
    (net (code "89") (name "Net-(Q5-B)") (class "Default")
      (node (ref "Q5") (pin "2") (pinfunction "B_2") (pintype "passive"))
      (node (ref "R41") (pin "1") (pinfunction "1_1") (pintype "passive"))
    )
    (net (code "90") (name "Net-(Q6-B)") (class "Default")
      (node (ref "Q6") (pin "2") (pinfunction "B_2") (pintype "passive"))
      (node (ref "R42") (pin "1") (pinfunction "1_1") (pintype "passive"))
    )
    (net (code "91") (name "Net-(Q7-B)") (class "Default")
      (node (ref "Q7") (pin "2") (pinfunction "B_2") (pintype "passive"))
      (node (ref "R43") (pin "1") (pinfunction "1_1") (pintype "passive"))
    )
    (net (code "92") (name "Net-(Q8-B)") (class "Default")
      (node (ref "Q8") (pin "2") (pinfunction "B_2") (pintype "passive"))
      (node (ref "R47") (pin "1") (pinfunction "1_1") (pintype "passive"))
    )
    (net (code "93") (name "Net-(U4-IO0_0)") (class "Default")
      (node (ref "R22") (pin "2") (pinfunction "2_2") (pintype "passive"))
      (node (ref "U4") (pin "4") (pinfunction "IO0_0_4") (pintype "passive"))
    )
    (net (code "94") (name "Net-(U4-IO0_1)") (class "Default")
      (node (ref "R23") (pin "2") (pinfunction "2_2") (pintype "passive"))
      (node (ref "U4") (pin "5") (pinfunction "IO0_1_5") (pintype "passive"))
    )
    (net (code "95") (name "Net-(U4-IO0_2)") (class "Default")
      (node (ref "R25") (pin "2") (pinfunction "2_2") (pintype "passive"))
      (node (ref "U4") (pin "6") (pinfunction "IO0_2_6") (pintype "passive"))
    )
    (net (code "96") (name "Net-(U4-IO0_3)") (class "Default")
      (node (ref "R27") (pin "2") (pinfunction "2_2") (pintype "passive"))
      (node (ref "U4") (pin "7") (pinfunction "IO0_3_7") (pintype "passive"))
    )
    (net (code "97") (name "Net-(U4-IO0_4)") (class "Default")
      (node (ref "R30") (pin "2") (pinfunction "2_2") (pintype "passive"))
      (node (ref "U4") (pin "8") (pinfunction "IO0_4_8") (pintype "passive"))
    )
    (net (code "98") (name "Net-(U4-IO0_5)") (class "Default")
      (node (ref "R32") (pin "2") (pinfunction "2_2") (pintype "passive"))
      (node (ref "U4") (pin "9") (pinfunction "IO0_5_9") (pintype "passive"))
    )
    (net (code "99") (name "Net-(U4-IO0_6)") (class "Default")
      (node (ref "R34") (pin "2") (pinfunction "2_2") (pintype "passive"))
      (node (ref "U4") (pin "10") (pinfunction "IO0_6_10") (pintype "passive"))
    )
    (net (code "100") (name "Net-(U4-IO0_7)") (class "Default")
      (node (ref "R36") (pin "2") (pinfunction "2_2") (pintype "passive"))
      (node (ref "U4") (pin "11") (pinfunction "IO0_7_11") (pintype "passive"))
    )
    (net (code "101") (name "Net-(U4-IO1_0)") (class "Default")
      (node (ref "R38") (pin "1") (pinfunction "1_1") (pintype "passive"))
      (node (ref "U4") (pin "13") (pinfunction "IO1_0_13") (pintype "passive"))
    )
    (net (code "102") (name "Net-(U4-IO1_1)") (class "Default")
      (node (ref "R37") (pin "1") (pinfunction "1_1") (pintype "passive"))
      (node (ref "U4") (pin "14") (pinfunction "IO1_1_14") (pintype "passive"))
    )
    (net (code "103") (name "Net-(U4-IO1_2)") (class "Default")
      (node (ref "R35") (pin "1") (pinfunction "1_1") (pintype "passive"))
      (node (ref "U4") (pin "15") (pinfunction "IO1_2_15") (pintype "passive"))
    )
    (net (code "104") (name "Net-(U4-IO1_3)") (class "Default")
      (node (ref "R33") (pin "1") (pinfunction "1_1") (pintype "passive"))
      (node (ref "U4") (pin "16") (pinfunction "IO1_3_16") (pintype "passive"))
    )
    (net (code "105") (name "Net-(U4-IO1_4)") (class "Default")
      (node (ref "R31") (pin "1") (pinfunction "1_1") (pintype "passive"))
      (node (ref "U4") (pin "17") (pinfunction "IO1_4_17") (pintype "passive"))
    )
    (net (code "106") (name "Net-(U4-IO1_5)") (class "Default")
      (node (ref "R28") (pin "1") (pinfunction "1_1") (pintype "passive"))
      (node (ref "U4") (pin "18") (pinfunction "IO1_5_18") (pintype "passive"))
    )
    (net (code "107") (name "Net-(U4-IO1_6)") (class "Default")
      (node (ref "R26") (pin "1") (pinfunction "1_1") (pintype "passive"))
      (node (ref "U4") (pin "19") (pinfunction "IO1_6_19") (pintype "passive"))
    )
    (net (code "108") (name "Net-(U4-IO1_7)") (class "Default")
      (node (ref "R24") (pin "1") (pinfunction "1_1") (pintype "passive"))
      (node (ref "U4") (pin "20") (pinfunction "IO1_7_20") (pintype "passive"))
    )
    (net (code "109") (name "Net-(U5-IO0_0)") (class "Default")
      (node (ref "R44") (pin "2") (pinfunction "2_2") (pintype "passive"))
      (node (ref "U5") (pin "4") (pinfunction "IO0_0_4") (pintype "passive"))
    )
    (net (code "110") (name "Net-(U5-IO0_1)") (class "Default")
      (node (ref "R45") (pin "2") (pinfunction "2_2") (pintype "passive"))
      (node (ref "U5") (pin "5") (pinfunction "IO0_1_5") (pintype "passive"))
    )
    (net (code "111") (name "Net-(U5-IO0_2)") (class "Default")
      (node (ref "R48") (pin "2") (pinfunction "2_2") (pintype "passive"))
      (node (ref "U5") (pin "6") (pinfunction "IO0_2_6") (pintype "passive"))
    )
    (net (code "112") (name "Net-(U5-IO0_3)") (class "Default")
      (node (ref "R50") (pin "2") (pinfunction "2_2") (pintype "passive"))
      (node (ref "U5") (pin "7") (pinfunction "IO0_3_7") (pintype "passive"))
    )
    (net (code "113") (name "Net-(U5-IO0_4)") (class "Default")
      (node (ref "R53") (pin "2") (pinfunction "2_2") (pintype "passive"))
      (node (ref "U5") (pin "8") (pinfunction "IO0_4_8") (pintype "passive"))
    )
    (net (code "114") (name "Net-(U5-IO0_5)") (class "Default")
      (node (ref "R57") (pin "2") (pinfunction "2_2") (pintype "passive"))
      (node (ref "U5") (pin "9") (pinfunction "IO0_5_9") (pintype "passive"))
    )
    (net (code "115") (name "Net-(U5-IO0_6)") (class "Default")
      (node (ref "R61") (pin "2") (pinfunction "2_2") (pintype "passive"))
      (node (ref "U5") (pin "10") (pinfunction "IO0_6_10") (pintype "passive"))
    )
    (net (code "116") (name "Net-(U5-IO0_7)") (class "Default")
      (node (ref "R65") (pin "2") (pinfunction "2_2") (pintype "passive"))
      (node (ref "U5") (pin "11") (pinfunction "IO0_7_11") (pintype "passive"))
    )
    (net (code "117") (name "Net-(U5-IO1_0)") (class "Default")
      (node (ref "R69") (pin "1") (pinfunction "1_1") (pintype "passive"))
      (node (ref "U5") (pin "13") (pinfunction "IO1_0_13") (pintype "passive"))
    )
    (net (code "118") (name "Net-(U5-IO1_1)") (class "Default")
      (node (ref "R66") (pin "1") (pinfunction "1_1") (pintype "passive"))
      (node (ref "U5") (pin "14") (pinfunction "IO1_1_14") (pintype "passive"))
    )
    (net (code "119") (name "Net-(U5-IO1_2)") (class "Default")
      (node (ref "R62") (pin "1") (pinfunction "1_1") (pintype "passive"))
      (node (ref "U5") (pin "15") (pinfunction "IO1_2_15") (pintype "passive"))
    )
    (net (code "120") (name "Net-(U5-IO1_3)") (class "Default")
      (node (ref "R58") (pin "1") (pinfunction "1_1") (pintype "passive"))
      (node (ref "U5") (pin "16") (pinfunction "IO1_3_16") (pintype "passive"))
    )
    (net (code "121") (name "Net-(U5-IO1_4)") (class "Default")
      (node (ref "R54") (pin "1") (pinfunction "1_1") (pintype "passive"))
      (node (ref "U5") (pin "17") (pinfunction "IO1_4_17") (pintype "passive"))
    )
    (net (code "122") (name "Net-(U5-IO1_5)") (class "Default")
      (node (ref "R51") (pin "1") (pinfunction "1_1") (pintype "passive"))
      (node (ref "U5") (pin "18") (pinfunction "IO1_5_18") (pintype "passive"))
    )
    (net (code "123") (name "Net-(U5-IO1_6)") (class "Default")
      (node (ref "R49") (pin "1") (pinfunction "1_1") (pintype "passive"))
      (node (ref "U5") (pin "19") (pinfunction "IO1_6_19") (pintype "passive"))
    )
    (net (code "124") (name "Net-(U5-IO1_7)") (class "Default")
      (node (ref "R46") (pin "1") (pinfunction "1_1") (pintype "passive"))
      (node (ref "U5") (pin "20") (pinfunction "IO1_7_20") (pintype "passive"))
    )
    (net (code "125") (name "Net-(U6-IO0_0)") (class "Default")
      (node (ref "R52") (pin "2") (pinfunction "2_2") (pintype "passive"))
      (node (ref "U6") (pin "4") (pinfunction "IO0_0_4") (pintype "passive"))
    )
    (net (code "126") (name "Net-(U6-IO0_1)") (class "Default")
      (node (ref "R55") (pin "2") (pinfunction "2_2") (pintype "passive"))
      (node (ref "U6") (pin "5") (pinfunction "IO0_1_5") (pintype "passive"))
    )
    (net (code "127") (name "Net-(U6-IO0_2)") (class "Default")
      (node (ref "R59") (pin "2") (pinfunction "2_2") (pintype "passive"))
      (node (ref "U6") (pin "6") (pinfunction "IO0_2_6") (pintype "passive"))
    )
    (net (code "128") (name "Net-(U6-IO0_3)") (class "Default")
      (node (ref "R63") (pin "2") (pinfunction "2_2") (pintype "passive"))
      (node (ref "U6") (pin "7") (pinfunction "IO0_3_7") (pintype "passive"))
    )
    (net (code "129") (name "Net-(U6-IO0_4)") (class "Default")
      (node (ref "R67") (pin "2") (pinfunction "2_2") (pintype "passive"))
      (node (ref "U6") (pin "8") (pinfunction "IO0_4_8") (pintype "passive"))
    )
    (net (code "130") (name "Net-(U6-IO0_5)") (class "Default")
      (node (ref "R71") (pin "2") (pinfunction "2_2") (pintype "passive"))
      (node (ref "U6") (pin "9") (pinfunction "IO0_5_9") (pintype "passive"))
    )
    (net (code "131") (name "Net-(U6-IO0_6)") (class "Default")
      (node (ref "R75") (pin "2") (pinfunction "2_2") (pintype "passive"))
      (node (ref "U6") (pin "10") (pinfunction "IO0_6_10") (pintype "passive"))
    )
    (net (code "132") (name "Net-(U6-IO0_7)") (class "Default")
      (node (ref "R79") (pin "2") (pinfunction "2_2") (pintype "passive"))
      (node (ref "U6") (pin "11") (pinfunction "IO0_7_11") (pintype "passive"))
    )
    (net (code "133") (name "Net-(U6-IO1_0)") (class "Default")
      (node (ref "R83") (pin "1") (pinfunction "1_1") (pintype "passive"))
      (node (ref "U6") (pin "13") (pinfunction "IO1_0_13") (pintype "passive"))
    )
    (net (code "134") (name "Net-(U6-IO1_1)") (class "Default")
      (node (ref "R80") (pin "1") (pinfunction "1_1") (pintype "passive"))
      (node (ref "U6") (pin "14") (pinfunction "IO1_1_14") (pintype "passive"))
    )
    (net (code "135") (name "Net-(U6-IO1_2)") (class "Default")
      (node (ref "R76") (pin "1") (pinfunction "1_1") (pintype "passive"))
      (node (ref "U6") (pin "15") (pinfunction "IO1_2_15") (pintype "passive"))
    )
    (net (code "136") (name "Net-(U6-IO1_3)") (class "Default")
      (node (ref "R72") (pin "1") (pinfunction "1_1") (pintype "passive"))
      (node (ref "U6") (pin "16") (pinfunction "IO1_3_16") (pintype "passive"))
    )
    (net (code "137") (name "Net-(U6-IO1_4)") (class "Default")
      (node (ref "R68") (pin "1") (pinfunction "1_1") (pintype "passive"))
      (node (ref "U6") (pin "17") (pinfunction "IO1_4_17") (pintype "passive"))
    )
    (net (code "138") (name "Net-(U6-IO1_5)") (class "Default")
      (node (ref "R64") (pin "1") (pinfunction "1_1") (pintype "passive"))
      (node (ref "U6") (pin "18") (pinfunction "IO1_5_18") (pintype "passive"))
    )
    (net (code "139") (name "Net-(U6-IO1_6)") (class "Default")
      (node (ref "R60") (pin "1") (pinfunction "1_1") (pintype "passive"))
      (node (ref "U6") (pin "19") (pinfunction "IO1_6_19") (pintype "passive"))
    )
    (net (code "140") (name "Net-(U6-IO1_7)") (class "Default")
      (node (ref "R56") (pin "1") (pinfunction "1_1") (pintype "passive"))
      (node (ref "U6") (pin "20") (pinfunction "IO1_7_20") (pintype "passive"))
    )
    (net (code "141") (name "Net-(U7-IO0_0)") (class "Default")
      (node (ref "R70") (pin "2") (pinfunction "2_2") (pintype "passive"))
      (node (ref "U7") (pin "4") (pinfunction "IO0_0_4") (pintype "passive"))
    )
    (net (code "142") (name "Net-(U7-IO0_1)") (class "Default")
      (node (ref "R73") (pin "2") (pinfunction "2_2") (pintype "passive"))
      (node (ref "U7") (pin "5") (pinfunction "IO0_1_5") (pintype "passive"))
    )
    (net (code "143") (name "Net-(U7-IO0_2)") (class "Default")
      (node (ref "R77") (pin "2") (pinfunction "2_2") (pintype "passive"))
      (node (ref "U7") (pin "6") (pinfunction "IO0_2_6") (pintype "passive"))
    )
    (net (code "144") (name "Net-(U7-IO0_3)") (class "Default")
      (node (ref "R81") (pin "2") (pinfunction "2_2") (pintype "passive"))
      (node (ref "U7") (pin "7") (pinfunction "IO0_3_7") (pintype "passive"))
    )
    (net (code "145") (name "Net-(U7-IO0_4)") (class "Default")
      (node (ref "R84") (pin "2") (pinfunction "2_2") (pintype "passive"))
      (node (ref "U7") (pin "8") (pinfunction "IO0_4_8") (pintype "passive"))
    )
    (net (code "146") (name "Net-(U7-IO0_5)") (class "Default")
      (node (ref "R86") (pin "2") (pinfunction "2_2") (pintype "passive"))
      (node (ref "U7") (pin "9") (pinfunction "IO0_5_9") (pintype "passive"))
    )
    (net (code "147") (name "Net-(U7-IO0_6)") (class "Default")
      (node (ref "R88") (pin "2") (pinfunction "2_2") (pintype "passive"))
      (node (ref "U7") (pin "10") (pinfunction "IO0_6_10") (pintype "passive"))
    )
    (net (code "148") (name "Net-(U7-IO0_7)") (class "Default")
      (node (ref "R90") (pin "2") (pinfunction "2_2") (pintype "passive"))
      (node (ref "U7") (pin "11") (pinfunction "IO0_7_11") (pintype "passive"))
    )
    (net (code "149") (name "Net-(U7-IO1_0)") (class "Default")
      (node (ref "R92") (pin "1") (pinfunction "1_1") (pintype "passive"))
      (node (ref "U7") (pin "13") (pinfunction "IO1_0_13") (pintype "passive"))
    )
    (net (code "150") (name "Net-(U7-IO1_1)") (class "Default")
      (node (ref "R91") (pin "1") (pinfunction "1_1") (pintype "passive"))
      (node (ref "U7") (pin "14") (pinfunction "IO1_1_14") (pintype "passive"))
    )
    (net (code "151") (name "Net-(U7-IO1_2)") (class "Default")
      (node (ref "R89") (pin "1") (pinfunction "1_1") (pintype "passive"))
      (node (ref "U7") (pin "15") (pinfunction "IO1_2_15") (pintype "passive"))
    )
    (net (code "152") (name "Net-(U7-IO1_3)") (class "Default")
      (node (ref "R87") (pin "1") (pinfunction "1_1") (pintype "passive"))
      (node (ref "U7") (pin "16") (pinfunction "IO1_3_16") (pintype "passive"))
    )
    (net (code "153") (name "Net-(U7-IO1_4)") (class "Default")
      (node (ref "R85") (pin "1") (pinfunction "1_1") (pintype "passive"))
      (node (ref "U7") (pin "17") (pinfunction "IO1_4_17") (pintype "passive"))
    )
    (net (code "154") (name "Net-(U7-IO1_5)") (class "Default")
      (node (ref "R82") (pin "1") (pinfunction "1_1") (pintype "passive"))
      (node (ref "U7") (pin "18") (pinfunction "IO1_5_18") (pintype "passive"))
    )
    (net (code "155") (name "Net-(U7-IO1_6)") (class "Default")
      (node (ref "R78") (pin "1") (pinfunction "1_1") (pintype "passive"))
      (node (ref "U7") (pin "19") (pinfunction "IO1_6_19") (pintype "passive"))
    )
    (net (code "156") (name "Net-(U7-IO1_7)") (class "Default")
      (node (ref "R74") (pin "1") (pinfunction "1_1") (pintype "passive"))
      (node (ref "U7") (pin "20") (pinfunction "IO1_7_20") (pintype "passive"))
    )
    (net (code "157") (name "unconnected-(U4-~{INT}-Pad1)") (class "Default")
      (node (ref "U4") (pin "1") (pinfunction "~{INT}_1") (pintype "passive"))
    )
    (net (code "158") (name "unconnected-(U5-~{INT}-Pad1)") (class "Default")
      (node (ref "U5") (pin "1") (pinfunction "~{INT}_1") (pintype "passive"))
    )
    (net (code "159") (name "unconnected-(U6-~{INT}-Pad1)") (class "Default")
      (node (ref "U6") (pin "1") (pinfunction "~{INT}_1") (pintype "passive"))
    )
    (net (code "160") (name "unconnected-(U7-~{INT}-Pad1)") (class "Default")
      (node (ref "U7") (pin "1") (pinfunction "~{INT}_1") (pintype "passive"))
    )
  )
)
